# wifiCPUnew.net
KiCad netlist of a schematic drawn in EAGLE
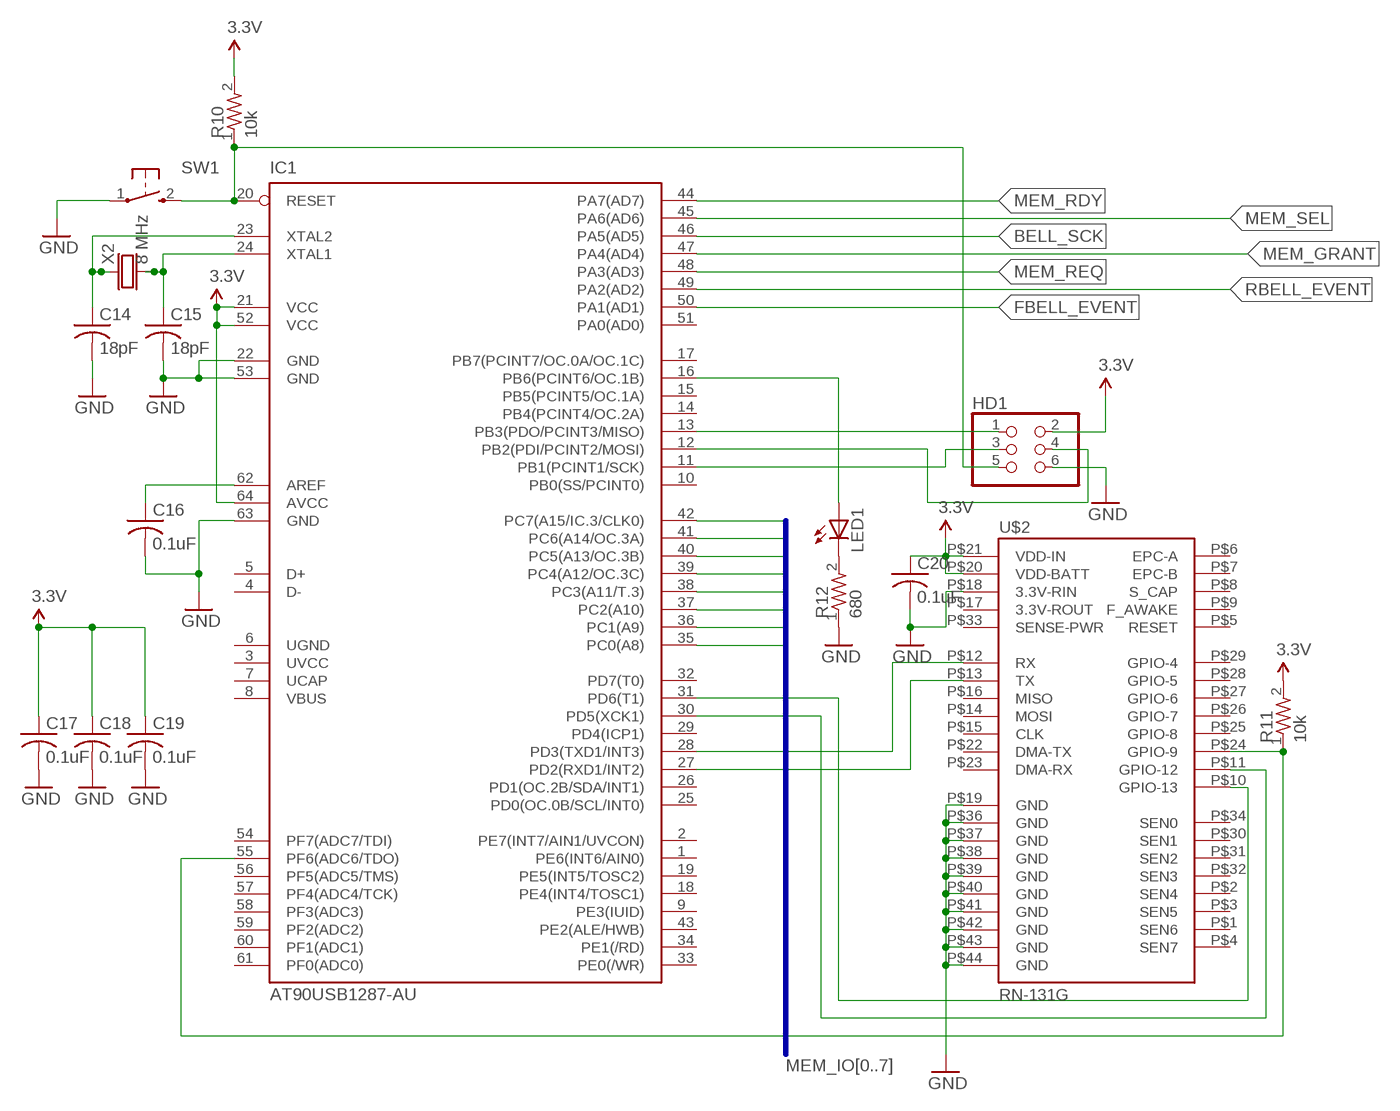
[diagram p0: schematic, sheet 1]

(export (version "E")
  (design (tool "Eeschema 10.0.6"))
  (components
    (comp (ref "C14")
      (value "18pF")
      (footprint "eagle-import:0603_RESISTOR")
      (libsource (lib "eagle-import") (part "0603_CAP"))
    )
    (comp (ref "C15")
      (value "18pF")
      (footprint "eagle-import:0603_RESISTOR")
      (libsource (lib "eagle-import") (part "0603_CAP"))
    )
    (comp (ref "C16")
      (value "0.1uF")
      (footprint "eagle-import:0603_RESISTOR")
      (libsource (lib "eagle-import") (part "0603_CAP"))
    )
    (comp (ref "C17")
      (value "0.1uF")
      (footprint "eagle-import:0603_RESISTOR")
      (libsource (lib "eagle-import") (part "0603_CAP"))
    )
    (comp (ref "C18")
      (value "0.1uF")
      (footprint "eagle-import:0603_RESISTOR")
      (libsource (lib "eagle-import") (part "0603_CAP"))
    )
    (comp (ref "C19")
      (value "0.1uF")
      (footprint "eagle-import:0603_RESISTOR")
      (libsource (lib "eagle-import") (part "0603_CAP"))
    )
    (comp (ref "C20")
      (value "0.1uF")
      (footprint "eagle-import:0603_RESISTOR")
      (libsource (lib "eagle-import") (part "0603_CAP"))
    )
    (comp (ref "HD1")
      (value "HEADER2X3")
      (footprint "eagle-import:HEADER2X3")
      (libsource (lib "eagle-import") (part "HEADER2X3"))
    )
    (comp (ref "IC1")
      (value "AT90USB1287-AU")
      (footprint "eagle-import:TQFP64")
      (libsource (lib "eagle-import") (part "AT90USB1287-AU"))
    )
    (comp (ref "LED1")
      (value "LEDCHIP-LED0603")
      (footprint "eagle-import:CHIP-LED0603")
      (libsource (lib "eagle-import") (part "LEDCHIP-LED0603"))
    )
    (comp (ref "R10")
      (value "10k")
      (footprint "eagle-import:0603_RESISTOR")
      (libsource (lib "eagle-import") (part "0603_RESISTOR"))
    )
    (comp (ref "R11")
      (value "10k")
      (footprint "eagle-import:0603_RESISTOR")
      (libsource (lib "eagle-import") (part "0603_RESISTOR"))
    )
    (comp (ref "R12")
      (value "680")
      (footprint "eagle-import:0603_RESISTOR")
      (libsource (lib "eagle-import") (part "0603_RESISTOR"))
    )
    (comp (ref "SW1")
      (value "TAC-SWITCH")
      (footprint "eagle-import:TAC-SWITCH")
      (libsource (lib "eagle-import") (part "TAC-SWITCH"))
    )
    (comp (ref "U$2")
      (value "RN-131G")
      (footprint "eagle-import:RN-131G")
      (libsource (lib "eagle-import") (part "RN-131G"))
    )
    (comp (ref "X2")
      (value "8 MHz")
      (footprint "eagle-import:CRYSTAL_5X3")
      (libsource (lib "eagle-import") (part "CRYSTAL_5X3"))
    )
  )
  (nets
    (net (code "10") (name "/UCAP") (class "Default")
      (node (ref "IC1") (pin "7") (pinfunction "UCAP_7") (pintype "power_in"))
    )
    (net (code "11") (name "/UGND") (class "Default")
      (node (ref "IC1") (pin "6") (pinfunction "UGND_6") (pintype "power_in"))
    )
    (net (code "12") (name "/UVCC") (class "Default")
      (node (ref "IC1") (pin "3") (pinfunction "UVCC_3") (pintype "power_in"))
    )
    (net (code "13") (name "/VBUS") (class "Default")
      (node (ref "IC1") (pin "8") (pinfunction "VBUS_8") (pintype "power_in"))
    )
    (net (code "14") (name "3.3V") (class "Default")
      (node (ref "C17") (pin "1") (pinfunction "1_1") (pintype "passive"))
      (node (ref "C18") (pin "1") (pinfunction "1_1") (pintype "passive"))
      (node (ref "C19") (pin "1") (pinfunction "1_1") (pintype "passive"))
      (node (ref "C20") (pin "1") (pinfunction "1_1") (pintype "passive"))
      (node (ref "HD1") (pin "2") (pinfunction "2_2") (pintype "passive"))
      (node (ref "IC1") (pin "21") (pinfunction "VCC_21") (pintype "power_in"))
      (node (ref "IC1") (pin "52") (pinfunction "VCC_52") (pintype "power_in"))
      (node (ref "IC1") (pin "64") (pinfunction "AVCC_64") (pintype "bidirectional"))
      (node (ref "R10") (pin "2") (pinfunction "2_2") (pintype "passive"))
      (node (ref "R11") (pin "2") (pinfunction "2_2") (pintype "passive"))
      (node (ref "U$2") (pin "P$20") (pinfunction "VDD-BATT_P$20") (pintype "bidirectional"))
      (node (ref "U$2") (pin "P$21") (pinfunction "VDD-IN_P$21") (pintype "bidirectional"))
    )
    (net (code "15") (name "BELL_SCK") (class "Default")
      (node (ref "IC1") (pin "46") (pinfunction "PA5(AD5)_46") (pintype "bidirectional"))
    )
    (net (code "16") (name "FBELL_EVENT") (class "Default")
      (node (ref "IC1") (pin "50") (pinfunction "PA1(AD1)_50") (pintype "bidirectional"))
    )
    (net (code "17") (name "GND") (class "Default")
      (node (ref "C14") (pin "2") (pinfunction "2_2") (pintype "passive"))
      (node (ref "C15") (pin "2") (pinfunction "2_2") (pintype "passive"))
      (node (ref "C16") (pin "2") (pinfunction "2_2") (pintype "passive"))
      (node (ref "C17") (pin "2") (pinfunction "2_2") (pintype "passive"))
      (node (ref "C18") (pin "2") (pinfunction "2_2") (pintype "passive"))
      (node (ref "C19") (pin "2") (pinfunction "2_2") (pintype "passive"))
      (node (ref "C20") (pin "2") (pinfunction "2_2") (pintype "passive"))
      (node (ref "HD1") (pin "6") (pinfunction "6_6") (pintype "passive"))
      (node (ref "IC1") (pin "22") (pinfunction "GND_22") (pintype "power_in"))
      (node (ref "IC1") (pin "53") (pinfunction "GND_53") (pintype "power_in"))
      (node (ref "IC1") (pin "63") (pinfunction "GND_63") (pintype "power_in"))
      (node (ref "R12") (pin "1") (pinfunction "1_1") (pintype "passive"))
      (node (ref "SW1") (pin "1") (pinfunction "1_1") (pintype "passive"))
      (node (ref "U$2") (pin "P$18") (pinfunction "3.3V-RIN_P$18") (pintype "bidirectional"))
      (node (ref "U$2") (pin "P$19") (pinfunction "GND_P$19") (pintype "bidirectional"))
      (node (ref "U$2") (pin "P$36") (pinfunction "GND_P$36") (pintype "bidirectional"))
      (node (ref "U$2") (pin "P$37") (pinfunction "GND_P$37") (pintype "bidirectional"))
      (node (ref "U$2") (pin "P$38") (pinfunction "GND_P$38") (pintype "bidirectional"))
      (node (ref "U$2") (pin "P$39") (pinfunction "GND_P$39") (pintype "bidirectional"))
      (node (ref "U$2") (pin "P$40") (pinfunction "GND_P$40") (pintype "bidirectional"))
      (node (ref "U$2") (pin "P$41") (pinfunction "GND_P$41") (pintype "bidirectional"))
      (node (ref "U$2") (pin "P$42") (pinfunction "GND_P$42") (pintype "bidirectional"))
      (node (ref "U$2") (pin "P$43") (pinfunction "GND_P$43") (pintype "bidirectional"))
      (node (ref "U$2") (pin "P$44") (pinfunction "GND_P$44") (pintype "bidirectional"))
    )
    (net (code "18") (name "MEM_GRANT") (class "Default")
      (node (ref "IC1") (pin "47") (pinfunction "PA4(AD4)_47") (pintype "bidirectional"))
    )
    (net (code "19") (name "MEM_RDY") (class "Default")
      (node (ref "IC1") (pin "44") (pinfunction "PA7(AD7)_44") (pintype "bidirectional"))
    )
    (net (code "20") (name "MEM_REQ") (class "Default")
      (node (ref "IC1") (pin "48") (pinfunction "PA3(AD3)_48") (pintype "bidirectional"))
    )
    (net (code "21") (name "MEM_SEL") (class "Default")
      (node (ref "IC1") (pin "45") (pinfunction "PA6(AD6)_45") (pintype "bidirectional"))
    )
    (net (code "22") (name "Net-(IC1-AREF)") (class "Default")
      (node (ref "C16") (pin "1") (pinfunction "1_1") (pintype "passive"))
      (node (ref "IC1") (pin "62") (pinfunction "AREF_62") (pintype "bidirectional"))
    )
    (net (code "23") (name "Net-(IC1-PB1(PCINT1{slash}SCK))") (class "Default")
      (node (ref "HD1") (pin "3") (pinfunction "3_3") (pintype "passive"))
      (node (ref "IC1") (pin "11") (pinfunction "PB1(PCINT1/SCK)_11") (pintype "bidirectional"))
    )
    (net (code "24") (name "Net-(IC1-PB2(PDI{slash}PCINT2{slash}MOSI))") (class "Default")
      (node (ref "HD1") (pin "4") (pinfunction "4_4") (pintype "passive"))
      (node (ref "IC1") (pin "12") (pinfunction "PB2(PDI/PCINT2/MOSI)_12") (pintype "bidirectional"))
    )
    (net (code "25") (name "Net-(IC1-PB3(PDO{slash}PCINT3{slash}MISO))") (class "Default")
      (node (ref "HD1") (pin "1") (pinfunction "1_1") (pintype "passive"))
      (node (ref "IC1") (pin "13") (pinfunction "PB3(PDO/PCINT3/MISO)_13") (pintype "bidirectional"))
    )
    (net (code "26") (name "Net-(IC1-PB6(PCINT6{slash}OC.1B))") (class "Default")
      (node (ref "IC1") (pin "16") (pinfunction "PB6(PCINT6/OC.1B)_16") (pintype "bidirectional"))
      (node (ref "LED1") (pin "A") (pinfunction "A_A") (pintype "passive"))
    )
    (net (code "27") (name "Net-(IC1-PD2(RXD1{slash}INT2))") (class "Default")
      (node (ref "IC1") (pin "27") (pinfunction "PD2(RXD1/INT2)_27") (pintype "bidirectional"))
      (node (ref "U$2") (pin "P$13") (pinfunction "TX_P$13") (pintype "bidirectional"))
    )
    (net (code "28") (name "Net-(IC1-PD3(TXD1{slash}INT3))") (class "Default")
      (node (ref "IC1") (pin "28") (pinfunction "PD3(TXD1/INT3)_28") (pintype "bidirectional"))
      (node (ref "U$2") (pin "P$12") (pinfunction "RX_P$12") (pintype "bidirectional"))
    )
    (net (code "29") (name "Net-(IC1-PD5(XCK1))") (class "Default")
      (node (ref "IC1") (pin "30") (pinfunction "PD5(XCK1)_30") (pintype "bidirectional"))
      (node (ref "U$2") (pin "P$11") (pinfunction "GPIO-12_P$11") (pintype "bidirectional"))
    )
    (net (code "30") (name "Net-(IC1-PD6(T1))") (class "Default")
      (node (ref "IC1") (pin "31") (pinfunction "PD6(T1)_31") (pintype "bidirectional"))
      (node (ref "U$2") (pin "P$10") (pinfunction "GPIO-13_P$10") (pintype "bidirectional"))
    )
    (net (code "31") (name "Net-(IC1-PF6(ADC6{slash}TDO))") (class "Default")
      (node (ref "IC1") (pin "55") (pinfunction "PF6(ADC6/TDO)_55") (pintype "bidirectional"))
      (node (ref "R11") (pin "1") (pinfunction "1_1") (pintype "passive"))
      (node (ref "U$2") (pin "P$24") (pinfunction "GPIO-9_P$24") (pintype "bidirectional"))
    )
    (net (code "32") (name "Net-(IC1-RESET)") (class "Default")
      (node (ref "HD1") (pin "5") (pinfunction "5_5") (pintype "passive"))
      (node (ref "IC1") (pin "20") (pinfunction "RESET_20") (pintype "input"))
      (node (ref "R10") (pin "1") (pinfunction "1_1") (pintype "passive"))
      (node (ref "SW1") (pin "2") (pinfunction "2_2") (pintype "passive"))
    )
    (net (code "33") (name "Net-(IC1-XTAL1)") (class "Default")
      (node (ref "C15") (pin "1") (pinfunction "1_1") (pintype "passive"))
      (node (ref "IC1") (pin "24") (pinfunction "XTAL1_24") (pintype "bidirectional"))
      (node (ref "X2") (pin "2") (pinfunction "2_2") (pintype "passive"))
    )
    (net (code "34") (name "Net-(IC1-XTAL2)") (class "Default")
      (node (ref "C14") (pin "1") (pinfunction "1_1") (pintype "passive"))
      (node (ref "IC1") (pin "23") (pinfunction "XTAL2_23") (pintype "bidirectional"))
      (node (ref "X2") (pin "1") (pinfunction "1_1") (pintype "passive"))
    )
    (net (code "35") (name "Net-(LED1-PadC)") (class "Default")
      (node (ref "LED1") (pin "C") (pinfunction "C_C") (pintype "passive"))
      (node (ref "R12") (pin "2") (pinfunction "2_2") (pintype "passive"))
    )
    (net (code "36") (name "RBELL_EVENT") (class "Default")
      (node (ref "IC1") (pin "49") (pinfunction "PA2(AD2)_49") (pintype "bidirectional"))
    )
    (net (code "37") (name "unconnected-(IC1-D+-Pad5)") (class "Default")
      (node (ref "IC1") (pin "5") (pinfunction "D+_5") (pintype "bidirectional"))
    )
    (net (code "38") (name "unconnected-(IC1-D--Pad4)") (class "Default")
      (node (ref "IC1") (pin "4") (pinfunction "D-_4") (pintype "bidirectional"))
    )
    (net (code "39") (name "unconnected-(IC1-PA0(AD0)-Pad51)") (class "Default")
      (node (ref "IC1") (pin "51") (pinfunction "PA0(AD0)_51") (pintype "bidirectional"))
    )
    (net (code "40") (name "unconnected-(IC1-PB0(SS{slash}PCINT0)-Pad10)") (class "Default")
      (node (ref "IC1") (pin "10") (pinfunction "PB0(SS/PCINT0)_10") (pintype "bidirectional"))
    )
    (net (code "41") (name "unconnected-(IC1-PB4(PCINT4{slash}OC.2A)-Pad14)") (class "Default")
      (node (ref "IC1") (pin "14") (pinfunction "PB4(PCINT4/OC.2A)_14") (pintype "bidirectional"))
    )
    (net (code "42") (name "unconnected-(IC1-PB5(PCINT5{slash}OC.1A)-Pad15)") (class "Default")
      (node (ref "IC1") (pin "15") (pinfunction "PB5(PCINT5/OC.1A)_15") (pintype "bidirectional"))
    )
    (net (code "43") (name "unconnected-(IC1-PB7(PCINT7{slash}OC.0A{slash}OC.1C)-Pad17)") (class "Default")
      (node (ref "IC1") (pin "17") (pinfunction "PB7(PCINT7/OC.0A/OC.1C)_17") (pintype "bidirectional"))
    )
    (net (code "44") (name "unconnected-(IC1-PC0(A8)-Pad35)") (class "Default")
      (node (ref "IC1") (pin "35") (pinfunction "PC0(A8)_35") (pintype "bidirectional"))
    )
    (net (code "45") (name "unconnected-(IC1-PC1(A9)-Pad36)") (class "Default")
      (node (ref "IC1") (pin "36") (pinfunction "PC1(A9)_36") (pintype "bidirectional"))
    )
    (net (code "46") (name "unconnected-(IC1-PC2(A10)-Pad37)") (class "Default")
      (node (ref "IC1") (pin "37") (pinfunction "PC2(A10)_37") (pintype "bidirectional"))
    )
    (net (code "47") (name "unconnected-(IC1-PC3(A11{slash}T.3)-Pad38)") (class "Default")
      (node (ref "IC1") (pin "38") (pinfunction "PC3(A11/T.3)_38") (pintype "bidirectional"))
    )
    (net (code "48") (name "unconnected-(IC1-PC4(A12{slash}OC.3C)-Pad39)") (class "Default")
      (node (ref "IC1") (pin "39") (pinfunction "PC4(A12/OC.3C)_39") (pintype "bidirectional"))
    )
    (net (code "49") (name "unconnected-(IC1-PC5(A13{slash}OC.3B)-Pad40)") (class "Default")
      (node (ref "IC1") (pin "40") (pinfunction "PC5(A13/OC.3B)_40") (pintype "bidirectional"))
    )
    (net (code "50") (name "unconnected-(IC1-PC6(A14{slash}OC.3A)-Pad41)") (class "Default")
      (node (ref "IC1") (pin "41") (pinfunction "PC6(A14/OC.3A)_41") (pintype "bidirectional"))
    )
    (net (code "51") (name "unconnected-(IC1-PC7(A15{slash}IC.3{slash}CLK0)-Pad42)") (class "Default")
      (node (ref "IC1") (pin "42") (pinfunction "PC7(A15/IC.3/CLK0)_42") (pintype "bidirectional"))
    )
    (net (code "52") (name "unconnected-(IC1-PD0(OC.0B{slash}SCL{slash}INT0)-Pad25)") (class "Default")
      (node (ref "IC1") (pin "25") (pinfunction "PD0(OC.0B/SCL/INT0)_25") (pintype "bidirectional"))
    )
    (net (code "53") (name "unconnected-(IC1-PD1(OC.2B{slash}SDA{slash}INT1)-Pad26)") (class "Default")
      (node (ref "IC1") (pin "26") (pinfunction "PD1(OC.2B/SDA/INT1)_26") (pintype "bidirectional"))
    )
    (net (code "54") (name "unconnected-(IC1-PD4(ICP1)-Pad29)") (class "Default")
      (node (ref "IC1") (pin "29") (pinfunction "PD4(ICP1)_29") (pintype "bidirectional"))
    )
    (net (code "55") (name "unconnected-(IC1-PD7(T0)-Pad32)") (class "Default")
      (node (ref "IC1") (pin "32") (pinfunction "PD7(T0)_32") (pintype "bidirectional"))
    )
    (net (code "56") (name "unconnected-(IC1-PE0({slash}WR)-Pad33)") (class "Default")
      (node (ref "IC1") (pin "33") (pinfunction "PE0(/WR)_33") (pintype "bidirectional"))
    )
    (net (code "57") (name "unconnected-(IC1-PE1({slash}RD)-Pad34)") (class "Default")
      (node (ref "IC1") (pin "34") (pinfunction "PE1(/RD)_34") (pintype "bidirectional"))
    )
    (net (code "58") (name "unconnected-(IC1-PE2(ALE{slash}HWB)-Pad43)") (class "Default")
      (node (ref "IC1") (pin "43") (pinfunction "PE2(ALE/HWB)_43") (pintype "bidirectional"))
    )
    (net (code "59") (name "unconnected-(IC1-PE3(IUID)-Pad9)") (class "Default")
      (node (ref "IC1") (pin "9") (pinfunction "PE3(IUID)_9") (pintype "bidirectional"))
    )
    (net (code "60") (name "unconnected-(IC1-PE4(INT4{slash}TOSC1)-Pad18)") (class "Default")
      (node (ref "IC1") (pin "18") (pinfunction "PE4(INT4/TOSC1)_18") (pintype "bidirectional"))
    )
    (net (code "61") (name "unconnected-(IC1-PE5(INT5{slash}TOSC2)-Pad19)") (class "Default")
      (node (ref "IC1") (pin "19") (pinfunction "PE5(INT5/TOSC2)_19") (pintype "bidirectional"))
    )
    (net (code "62") (name "unconnected-(IC1-PE6(INT6{slash}AIN0)-Pad1)") (class "Default")
      (node (ref "IC1") (pin "1") (pinfunction "PE6(INT6/AIN0)_1") (pintype "bidirectional"))
    )
    (net (code "63") (name "unconnected-(IC1-PE7(INT7{slash}AIN1{slash}UVCON)-Pad2)") (class "Default")
      (node (ref "IC1") (pin "2") (pinfunction "PE7(INT7/AIN1/UVCON)_2") (pintype "bidirectional"))
    )
    (net (code "64") (name "unconnected-(IC1-PF0(ADC0)-Pad61)") (class "Default")
      (node (ref "IC1") (pin "61") (pinfunction "PF0(ADC0)_61") (pintype "bidirectional"))
    )
    (net (code "65") (name "unconnected-(IC1-PF1(ADC1)-Pad60)") (class "Default")
      (node (ref "IC1") (pin "60") (pinfunction "PF1(ADC1)_60") (pintype "bidirectional"))
    )
    (net (code "66") (name "unconnected-(IC1-PF2(ADC2)-Pad59)") (class "Default")
      (node (ref "IC1") (pin "59") (pinfunction "PF2(ADC2)_59") (pintype "bidirectional"))
    )
    (net (code "67") (name "unconnected-(IC1-PF3(ADC3)-Pad58)") (class "Default")
      (node (ref "IC1") (pin "58") (pinfunction "PF3(ADC3)_58") (pintype "bidirectional"))
    )
    (net (code "68") (name "unconnected-(IC1-PF4(ADC4{slash}TCK)-Pad57)") (class "Default")
      (node (ref "IC1") (pin "57") (pinfunction "PF4(ADC4/TCK)_57") (pintype "bidirectional"))
    )
    (net (code "69") (name "unconnected-(IC1-PF5(ADC5{slash}TMS)-Pad56)") (class "Default")
      (node (ref "IC1") (pin "56") (pinfunction "PF5(ADC5/TMS)_56") (pintype "bidirectional"))
    )
    (net (code "70") (name "unconnected-(IC1-PF7(ADC7{slash}TDI)-Pad54)") (class "Default")
      (node (ref "IC1") (pin "54") (pinfunction "PF7(ADC7/TDI)_54") (pintype "bidirectional"))
    )
    (net (code "71") (name "unconnected-(U$2-3.3V-ROUT-PadP$17)") (class "Default")
      (node (ref "U$2") (pin "P$17") (pinfunction "3.3V-ROUT_P$17") (pintype "bidirectional"))
    )
    (net (code "72") (name "unconnected-(U$2-CLK-PadP$15)") (class "Default")
      (node (ref "U$2") (pin "P$15") (pinfunction "CLK_P$15") (pintype "bidirectional"))
    )
    (net (code "73") (name "unconnected-(U$2-DMA-RX-PadP$23)") (class "Default")
      (node (ref "U$2") (pin "P$23") (pinfunction "DMA-RX_P$23") (pintype "bidirectional"))
    )
    (net (code "74") (name "unconnected-(U$2-DMA-TX-PadP$22)") (class "Default")
      (node (ref "U$2") (pin "P$22") (pinfunction "DMA-TX_P$22") (pintype "bidirectional"))
    )
    (net (code "75") (name "unconnected-(U$2-EPC-A-PadP$6)") (class "Default")
      (node (ref "U$2") (pin "P$6") (pinfunction "EPC-A_P$6") (pintype "bidirectional"))
    )
    (net (code "76") (name "unconnected-(U$2-EPC-B-PadP$7)") (class "Default")
      (node (ref "U$2") (pin "P$7") (pinfunction "EPC-B_P$7") (pintype "bidirectional"))
    )
    (net (code "77") (name "unconnected-(U$2-F_AWAKE-PadP$9)") (class "Default")
      (node (ref "U$2") (pin "P$9") (pinfunction "F_AWAKE_P$9") (pintype "bidirectional"))
    )
    (net (code "78") (name "unconnected-(U$2-GPIO-4-PadP$29)") (class "Default")
      (node (ref "U$2") (pin "P$29") (pinfunction "GPIO-4_P$29") (pintype "bidirectional"))
    )
    (net (code "79") (name "unconnected-(U$2-GPIO-5-PadP$28)") (class "Default")
      (node (ref "U$2") (pin "P$28") (pinfunction "GPIO-5_P$28") (pintype "bidirectional"))
    )
    (net (code "80") (name "unconnected-(U$2-GPIO-6-PadP$27)") (class "Default")
      (node (ref "U$2") (pin "P$27") (pinfunction "GPIO-6_P$27") (pintype "bidirectional"))
    )
    (net (code "81") (name "unconnected-(U$2-GPIO-7-PadP$26)") (class "Default")
      (node (ref "U$2") (pin "P$26") (pinfunction "GPIO-7_P$26") (pintype "bidirectional"))
    )
    (net (code "82") (name "unconnected-(U$2-GPIO-8-PadP$25)") (class "Default")
      (node (ref "U$2") (pin "P$25") (pinfunction "GPIO-8_P$25") (pintype "bidirectional"))
    )
    (net (code "83") (name "unconnected-(U$2-MISO-PadP$16)") (class "Default")
      (node (ref "U$2") (pin "P$16") (pinfunction "MISO_P$16") (pintype "bidirectional"))
    )
    (net (code "84") (name "unconnected-(U$2-MOSI-PadP$14)") (class "Default")
      (node (ref "U$2") (pin "P$14") (pinfunction "MOSI_P$14") (pintype "bidirectional"))
    )
    (net (code "85") (name "unconnected-(U$2-RESET-PadP$5)") (class "Default")
      (node (ref "U$2") (pin "P$5") (pinfunction "RESET_P$5") (pintype "bidirectional"))
    )
    (net (code "86") (name "unconnected-(U$2-SEN0-PadP$34)") (class "Default")
      (node (ref "U$2") (pin "P$34") (pinfunction "SEN0_P$34") (pintype "bidirectional"))
    )
    (net (code "87") (name "unconnected-(U$2-SEN1-PadP$30)") (class "Default")
      (node (ref "U$2") (pin "P$30") (pinfunction "SEN1_P$30") (pintype "bidirectional"))
    )
    (net (code "88") (name "unconnected-(U$2-SEN2-PadP$31)") (class "Default")
      (node (ref "U$2") (pin "P$31") (pinfunction "SEN2_P$31") (pintype "bidirectional"))
    )
    (net (code "89") (name "unconnected-(U$2-SEN3-PadP$32)") (class "Default")
      (node (ref "U$2") (pin "P$32") (pinfunction "SEN3_P$32") (pintype "bidirectional"))
    )
    (net (code "90") (name "unconnected-(U$2-SEN4-PadP$2)") (class "Default")
      (node (ref "U$2") (pin "P$2") (pinfunction "SEN4_P$2") (pintype "bidirectional"))
    )
    (net (code "91") (name "unconnected-(U$2-SEN5-PadP$3)") (class "Default")
      (node (ref "U$2") (pin "P$3") (pinfunction "SEN5_P$3") (pintype "bidirectional"))
    )
    (net (code "92") (name "unconnected-(U$2-SEN6-PadP$1)") (class "Default")
      (node (ref "U$2") (pin "P$1") (pinfunction "SEN6_P$1") (pintype "bidirectional"))
    )
    (net (code "93") (name "unconnected-(U$2-SEN7-PadP$4)") (class "Default")
      (node (ref "U$2") (pin "P$4") (pinfunction "SEN7_P$4") (pintype "bidirectional"))
    )
    (net (code "94") (name "unconnected-(U$2-SENSE-PWR-PadP$33)") (class "Default")
      (node (ref "U$2") (pin "P$33") (pinfunction "SENSE-PWR_P$33") (pintype "bidirectional"))
    )
    (net (code "95") (name "unconnected-(U$2-S_CAP-PadP$8)") (class "Default")
      (node (ref "U$2") (pin "P$8") (pinfunction "S_CAP_P$8") (pintype "bidirectional"))
    )
  )
)
